# offroad-cpu-hardware.net
KiCad netlist of a schematic drawn in EAGLE
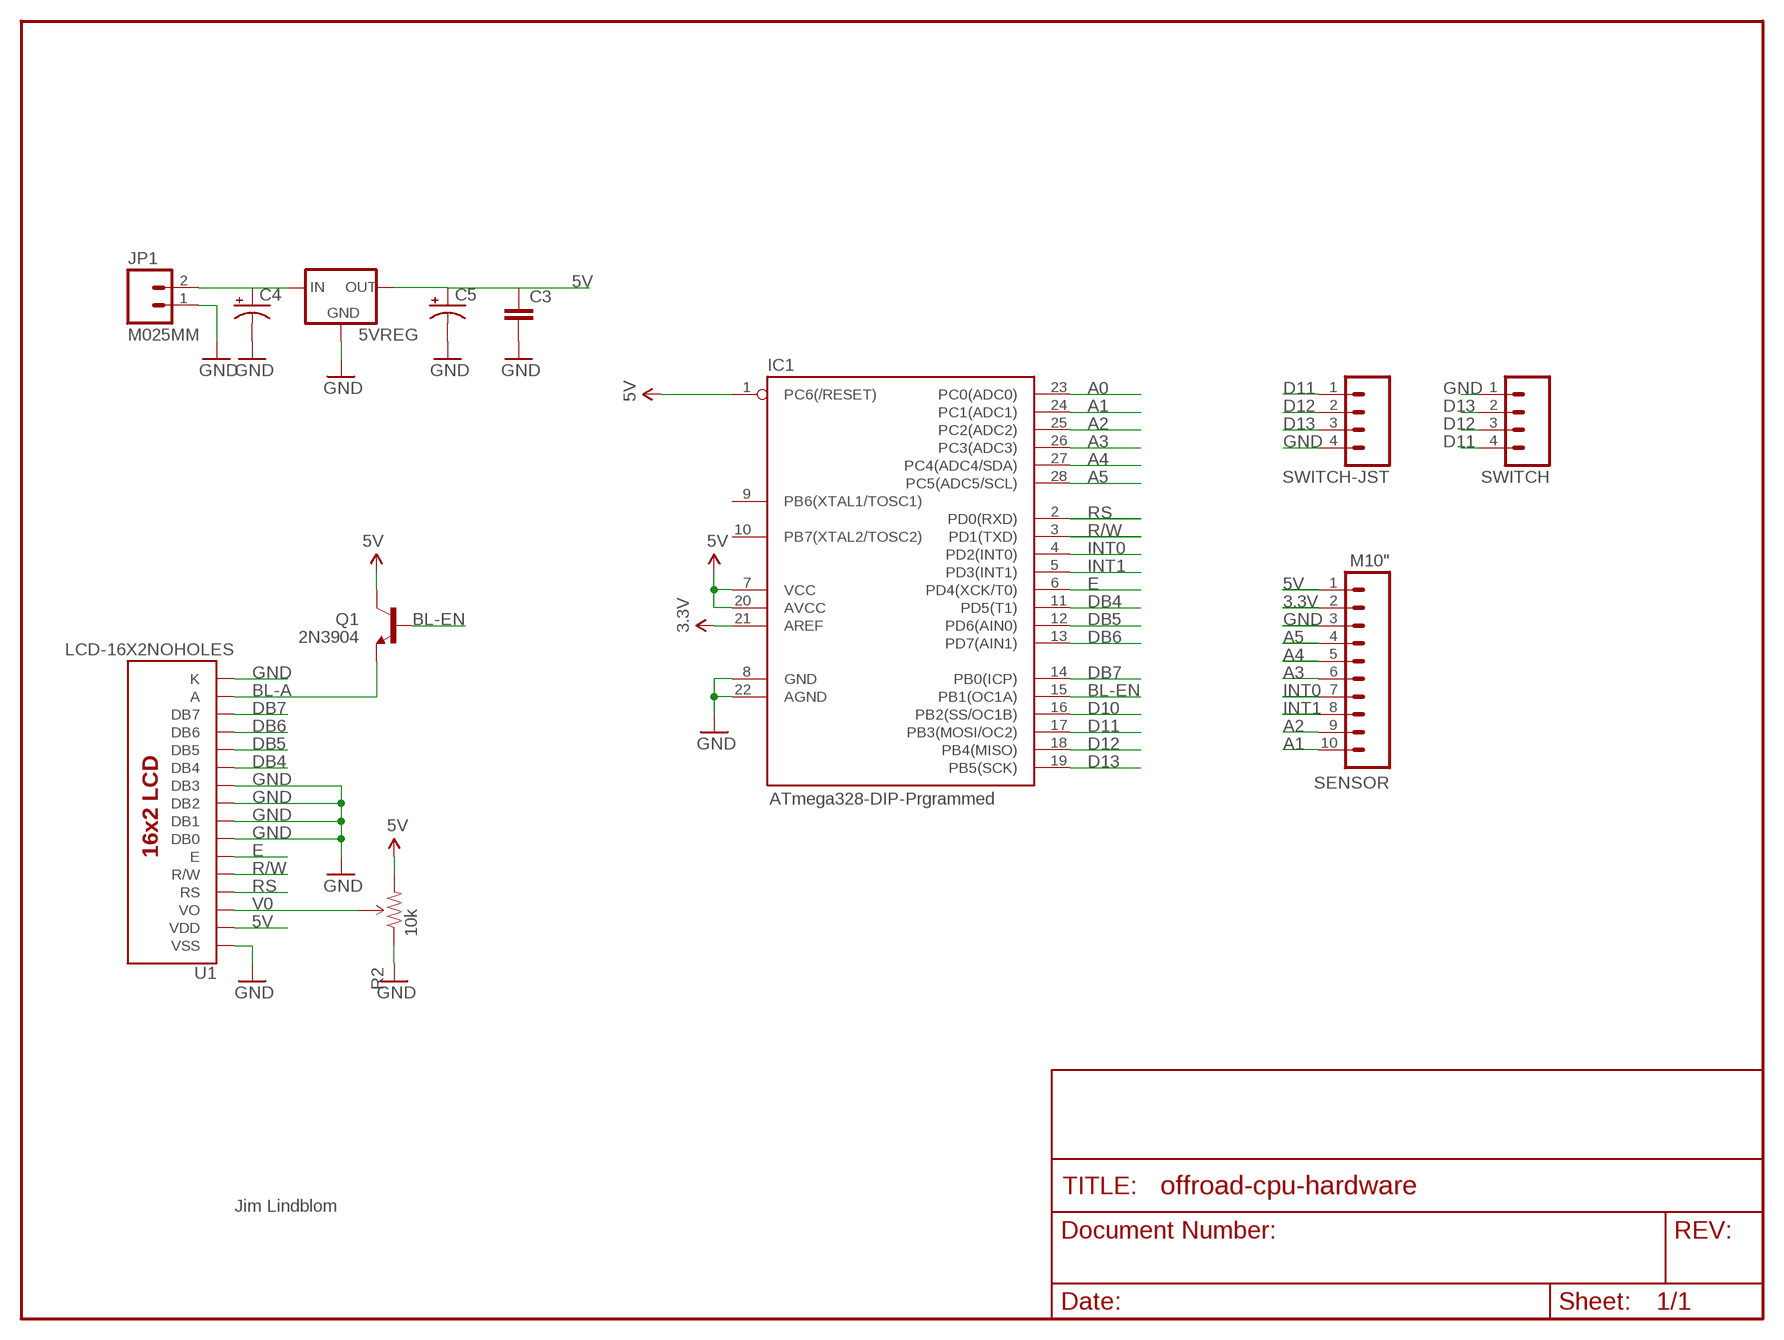
[diagram p0: schematic, sheet 1]

(export (version "E")
  (design (tool "Eeschema 10.0.6"))
  (components
    (comp (ref "5VREG")
      (value "78XXS")
      (footprint "eagle-import:78XXS")
      (libsource (lib "eagle-import") (part "78XXS"))
    )
    (comp (ref "C3")
      (value "CAPPTH2")
      (footprint "eagle-import:CAP-PTH-SMALL2")
      (libsource (lib "eagle-import") (part "CAPPTH2"))
    )
    (comp (ref "C4")
      (value "CAP_POLPTH2")
      (footprint "eagle-import:CPOL-RADIAL-10UF-25V")
      (libsource (lib "eagle-import") (part "CAP_POLPTH2"))
    )
    (comp (ref "C5")
      (value "CAP_POLPTH2")
      (footprint "eagle-import:CPOL-RADIAL-10UF-25V")
      (libsource (lib "eagle-import") (part "CAP_POLPTH2"))
    )
    (comp (ref "IC1")
      (value "ATmega328-DIP-Prgrammed")
      (footprint "eagle-import:DIL28-3")
      (libsource (lib "eagle-import") (part "AVR-MEGA8-PPTH"))
    )
    (comp (ref "JP1")
      (value "M025MM")
      (footprint "eagle-import:SCREWTERMINAL-5MM-2")
      (libsource (lib "eagle-import") (part "M025MM"))
    )
    (comp (ref "Q1")
      (value "2N3904")
      (footprint "eagle-import:TO-92")
      (libsource (lib "eagle-import") (part "TRANSISTOR_NPNTO92"))
    )
    (comp (ref "R2")
      (value "10k")
      (footprint "eagle-import:TRIM_POT_PTH")
      (libsource (lib "eagle-import") (part "TRIMPOTPTH"))
    )
    (comp (ref "SENSOR")
      (value "M10\"")
      (footprint "eagle-import:1X10")
      (libsource (lib "eagle-import") (part "M10{dblquote}"))
    )
    (comp (ref "SWITCH")
      (value "M04PTH")
      (footprint "eagle-import:1X04")
      (libsource (lib "eagle-import") (part "M04PTH"))
    )
    (comp (ref "SWITCH-JST")
      (value "M04JST-PTH")
      (footprint "eagle-import:JST-4-PTH")
      (libsource (lib "eagle-import") (part "M04JST-PTH"))
    )
    (comp (ref "U1")
      (value "LCD-16X2NOHOLES")
      (footprint "eagle-import:LCD-16X2_NOHOLES")
      (libsource (lib "eagle-import") (part "LCD-16X2NOHOLES"))
    )
  )
  (nets
    (net (code "1") (name "/A0") (class "Default")
      (node (ref "IC1") (pin "23") (pinfunction "PC0(ADC0)_23") (pintype "bidirectional"))
    )
    (net (code "2") (name "/A1") (class "Default")
      (node (ref "IC1") (pin "24") (pinfunction "PC1(ADC1)_24") (pintype "bidirectional"))
      (node (ref "SENSOR") (pin "10") (pinfunction "10_10") (pintype "passive"))
    )
    (net (code "3") (name "/A2") (class "Default")
      (node (ref "IC1") (pin "25") (pinfunction "PC2(ADC2)_25") (pintype "bidirectional"))
      (node (ref "SENSOR") (pin "9") (pinfunction "9_9") (pintype "passive"))
    )
    (net (code "4") (name "/A3") (class "Default")
      (node (ref "IC1") (pin "26") (pinfunction "PC3(ADC3)_26") (pintype "bidirectional"))
      (node (ref "SENSOR") (pin "6") (pinfunction "6_6") (pintype "passive"))
    )
    (net (code "5") (name "/A4") (class "Default")
      (node (ref "IC1") (pin "27") (pinfunction "PC4(ADC4/SDA)_27") (pintype "bidirectional"))
      (node (ref "SENSOR") (pin "5") (pinfunction "5_5") (pintype "passive"))
    )
    (net (code "6") (name "/A5") (class "Default")
      (node (ref "IC1") (pin "28") (pinfunction "PC5(ADC5/SCL)_28") (pintype "bidirectional"))
      (node (ref "SENSOR") (pin "4") (pinfunction "4_4") (pintype "passive"))
    )
    (net (code "7") (name "/BL-A") (class "Default")
      (node (ref "Q1") (pin "1") (pinfunction "E_1") (pintype "passive"))
      (node (ref "U1") (pin "15") (pinfunction "A_15") (pintype "power_in"))
    )
    (net (code "8") (name "/BL-EN") (class "Default")
      (node (ref "IC1") (pin "15") (pinfunction "PB1(OC1A)_15") (pintype "bidirectional"))
      (node (ref "Q1") (pin "2") (pinfunction "B_2") (pintype "passive"))
    )
    (net (code "9") (name "/D10") (class "Default")
      (node (ref "IC1") (pin "16") (pinfunction "PB2(SS/OC1B)_16") (pintype "bidirectional"))
    )
    (net (code "10") (name "/D11") (class "Default")
      (node (ref "IC1") (pin "17") (pinfunction "PB3(MOSI/OC2)_17") (pintype "bidirectional"))
      (node (ref "SWITCH") (pin "4") (pinfunction "4_4") (pintype "passive"))
      (node (ref "SWITCH-JST") (pin "1") (pinfunction "1_1") (pintype "passive"))
    )
    (net (code "11") (name "/D12") (class "Default")
      (node (ref "IC1") (pin "18") (pinfunction "PB4(MISO)_18") (pintype "bidirectional"))
      (node (ref "SWITCH") (pin "3") (pinfunction "3_3") (pintype "passive"))
      (node (ref "SWITCH-JST") (pin "2") (pinfunction "2_2") (pintype "passive"))
    )
    (net (code "12") (name "/D13") (class "Default")
      (node (ref "IC1") (pin "19") (pinfunction "PB5(SCK)_19") (pintype "bidirectional"))
      (node (ref "SWITCH") (pin "2") (pinfunction "2_2") (pintype "passive"))
      (node (ref "SWITCH-JST") (pin "3") (pinfunction "3_3") (pintype "passive"))
    )
    (net (code "13") (name "/DB4") (class "Default")
      (node (ref "IC1") (pin "11") (pinfunction "PD5(T1)_11") (pintype "bidirectional"))
      (node (ref "U1") (pin "11") (pinfunction "DB4_11") (pintype "bidirectional"))
    )
    (net (code "14") (name "/DB5") (class "Default")
      (node (ref "IC1") (pin "12") (pinfunction "PD6(AIN0)_12") (pintype "bidirectional"))
      (node (ref "U1") (pin "12") (pinfunction "DB5_12") (pintype "bidirectional"))
    )
    (net (code "15") (name "/DB6") (class "Default")
      (node (ref "IC1") (pin "13") (pinfunction "PD7(AIN1)_13") (pintype "bidirectional"))
      (node (ref "U1") (pin "13") (pinfunction "DB6_13") (pintype "bidirectional"))
    )
    (net (code "16") (name "/DB7") (class "Default")
      (node (ref "IC1") (pin "14") (pinfunction "PB0(ICP)_14") (pintype "bidirectional"))
      (node (ref "U1") (pin "14") (pinfunction "DB7_14") (pintype "bidirectional"))
    )
    (net (code "17") (name "/E") (class "Default")
      (node (ref "IC1") (pin "6") (pinfunction "PD4(XCK/T0)_6") (pintype "bidirectional"))
      (node (ref "U1") (pin "6") (pinfunction "E_6") (pintype "input"))
    )
    (net (code "18") (name "/INT0") (class "Default")
      (node (ref "IC1") (pin "4") (pinfunction "PD2(INT0)_4") (pintype "bidirectional"))
      (node (ref "SENSOR") (pin "7") (pinfunction "7_7") (pintype "passive"))
    )
    (net (code "19") (name "/INT1") (class "Default")
      (node (ref "IC1") (pin "5") (pinfunction "PD3(INT1)_5") (pintype "bidirectional"))
      (node (ref "SENSOR") (pin "8") (pinfunction "8_8") (pintype "passive"))
    )
    (net (code "20") (name "/RS") (class "Default")
      (node (ref "IC1") (pin "2") (pinfunction "PD0(RXD)_2") (pintype "bidirectional"))
      (node (ref "U1") (pin "4") (pinfunction "RS_4") (pintype "input"))
    )
    (net (code "21") (name "/R{slash}W") (class "Default")
      (node (ref "IC1") (pin "3") (pinfunction "PD1(TXD)_3") (pintype "bidirectional"))
      (node (ref "U1") (pin "5") (pinfunction "R/W_5") (pintype "input"))
    )
    (net (code "22") (name "/V0") (class "Default")
      (node (ref "R2") (pin "2") (pinfunction "WIPER_2") (pintype "passive"))
      (node (ref "U1") (pin "3") (pinfunction "VO_3") (pintype "bidirectional"))
    )
    (net (code "23") (name "3.3V") (class "Default")
      (node (ref "IC1") (pin "21") (pinfunction "AREF_21") (pintype "bidirectional"))
      (node (ref "SENSOR") (pin "2") (pinfunction "2_2") (pintype "passive"))
    )
    (net (code "24") (name "5V") (class "Default")
      (node (ref "5VREG") (pin "OUT") (pinfunction "OUT_OUT") (pintype "passive"))
      (node (ref "C3") (pin "1") (pinfunction "1_1") (pintype "passive"))
      (node (ref "C5") (pin "1") (pinfunction "+_1") (pintype "passive"))
      (node (ref "IC1") (pin "1") (pinfunction "PC6(/RESET)_1") (pintype "bidirectional"))
      (node (ref "IC1") (pin "20") (pinfunction "AVCC_20") (pintype "bidirectional"))
      (node (ref "IC1") (pin "7") (pinfunction "VCC_7") (pintype "bidirectional"))
      (node (ref "Q1") (pin "3") (pinfunction "C_3") (pintype "passive"))
      (node (ref "R2") (pin "3") (pinfunction "CW_3") (pintype "passive"))
      (node (ref "SENSOR") (pin "1") (pinfunction "1_1") (pintype "passive"))
      (node (ref "U1") (pin "2") (pinfunction "VDD_2") (pintype "power_in"))
    )
    (net (code "25") (name "GND") (class "Default")
      (node (ref "5VREG") (pin "GND") (pinfunction "GND_GND") (pintype "input"))
      (node (ref "C3") (pin "2") (pinfunction "2_2") (pintype "passive"))
      (node (ref "C4") (pin "2") (pinfunction "-_2") (pintype "passive"))
      (node (ref "C5") (pin "2") (pinfunction "-_2") (pintype "passive"))
      (node (ref "IC1") (pin "22") (pinfunction "AGND_22") (pintype "bidirectional"))
      (node (ref "IC1") (pin "8") (pinfunction "GND_8") (pintype "bidirectional"))
      (node (ref "JP1") (pin "1") (pinfunction "1_1") (pintype "passive"))
      (node (ref "R2") (pin "1") (pinfunction "CCW_1") (pintype "passive"))
      (node (ref "SENSOR") (pin "3") (pinfunction "3_3") (pintype "passive"))
      (node (ref "SWITCH") (pin "1") (pinfunction "1_1") (pintype "passive"))
      (node (ref "SWITCH-JST") (pin "4") (pinfunction "4_4") (pintype "passive"))
      (node (ref "U1") (pin "1") (pinfunction "VSS_1") (pintype "power_in"))
      (node (ref "U1") (pin "10") (pinfunction "DB3_10") (pintype "bidirectional"))
      (node (ref "U1") (pin "16") (pinfunction "K_16") (pintype "power_in"))
      (node (ref "U1") (pin "7") (pinfunction "DB0_7") (pintype "bidirectional"))
      (node (ref "U1") (pin "8") (pinfunction "DB1_8") (pintype "bidirectional"))
      (node (ref "U1") (pin "9") (pinfunction "DB2_9") (pintype "bidirectional"))
    )
    (net (code "26") (name "Net-(C4-+)") (class "Default")
      (node (ref "5VREG") (pin "IN") (pinfunction "IN_IN") (pintype "input"))
      (node (ref "C4") (pin "1") (pinfunction "+_1") (pintype "passive"))
      (node (ref "JP1") (pin "2") (pinfunction "2_2") (pintype "passive"))
    )
    (net (code "27") (name "unconnected-(IC1-PB6(XTAL1{slash}TOSC1)-Pad9)") (class "Default")
      (node (ref "IC1") (pin "9") (pinfunction "PB6(XTAL1/TOSC1)_9") (pintype "bidirectional"))
    )
    (net (code "28") (name "unconnected-(IC1-PB7(XTAL2{slash}TOSC2)-Pad10)") (class "Default")
      (node (ref "IC1") (pin "10") (pinfunction "PB7(XTAL2/TOSC2)_10") (pintype "bidirectional"))
    )
  )
)
